# XICIE_DISPLAY_revA.net
KiCad netlist of a schematic drawn in EAGLE
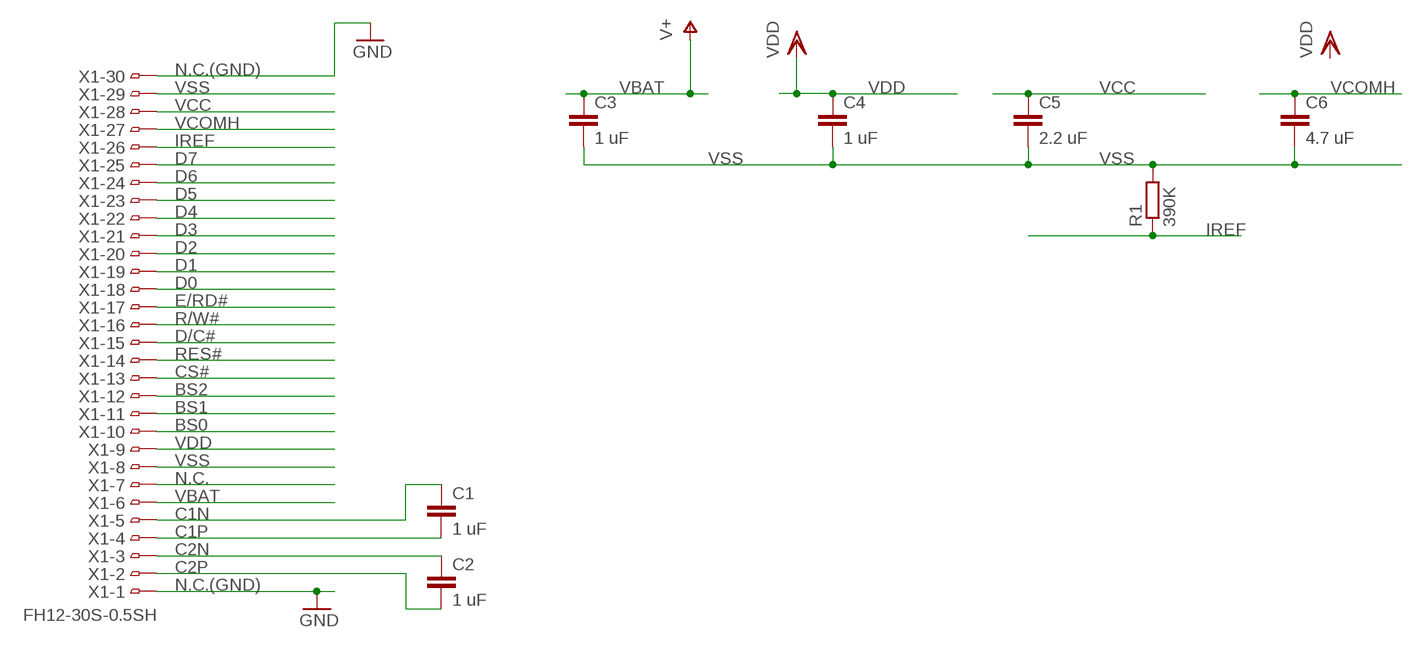
[diagram p0: schematic, sheet 1]

(export (version "E")
  (design (tool "Eeschema 10.0.6"))
  (components
    (comp (ref "C1")
      (value "1 uF")
      (footprint "eagle-import:C0402")
      (libsource (lib "eagle-import") (part "C-EUC0402"))
    )
    (comp (ref "C2")
      (value "1 uF")
      (footprint "eagle-import:C0402")
      (libsource (lib "eagle-import") (part "C-EUC0402"))
    )
    (comp (ref "C3")
      (value "1 uF")
      (footprint "eagle-import:C0402")
      (libsource (lib "eagle-import") (part "C-EUC0402"))
    )
    (comp (ref "C4")
      (value "1 uF")
      (footprint "eagle-import:C0402")
      (libsource (lib "eagle-import") (part "C-EUC0402"))
    )
    (comp (ref "C5")
      (value "2.2 uF")
      (footprint "eagle-import:C0603")
      (libsource (lib "eagle-import") (part "C-EUC0603"))
    )
    (comp (ref "C6")
      (value "4.7 uF")
      (footprint "eagle-import:C0603")
      (libsource (lib "eagle-import") (part "C-EUC0603"))
    )
    (comp (ref "R1")
      (value "390K")
      (footprint "eagle-import:R0603")
      (libsource (lib "eagle-import") (part "R-EU_R0603"))
    )
    (comp (ref "X1")
      (value "FH12-30S-0.5SH")
      (footprint "eagle-import:FH12-30S-0.5SH")
      (fields (field (name "MPN") "FH12-30S-0.5SH(55)"))
      (libsource (lib "eagle-import") (part "FH12-30S-0.5SH"))
    )
  )
  (nets
    (net (code "1") (name "/BS0") (class "Default")
      (node (ref "X1") (pin "10") (pinfunction "1_10") (pintype "passive"))
    )
    (net (code "2") (name "/BS1") (class "Default")
      (node (ref "X1") (pin "11") (pinfunction "1_11") (pintype "passive"))
    )
    (net (code "3") (name "/BS2") (class "Default")
      (node (ref "X1") (pin "12") (pinfunction "1_12") (pintype "passive"))
    )
    (net (code "4") (name "/C1N") (class "Default")
      (node (ref "C1") (pin "1") (pinfunction "1_1") (pintype "passive"))
      (node (ref "X1") (pin "5") (pinfunction "1_5") (pintype "passive"))
    )
    (net (code "5") (name "/C1P") (class "Default")
      (node (ref "C1") (pin "2") (pinfunction "2_2") (pintype "passive"))
      (node (ref "X1") (pin "4") (pinfunction "1_4") (pintype "passive"))
    )
    (net (code "6") (name "/C2N") (class "Default")
      (node (ref "C2") (pin "1") (pinfunction "1_1") (pintype "passive"))
      (node (ref "X1") (pin "3") (pinfunction "1_3") (pintype "passive"))
    )
    (net (code "7") (name "/C2P") (class "Default")
      (node (ref "C2") (pin "2") (pinfunction "2_2") (pintype "passive"))
      (node (ref "X1") (pin "2") (pinfunction "1_2") (pintype "passive"))
    )
    (net (code "8") (name "/CS#") (class "Default")
      (node (ref "X1") (pin "13") (pinfunction "1_13") (pintype "passive"))
    )
    (net (code "9") (name "/D0") (class "Default")
      (node (ref "X1") (pin "18") (pinfunction "1_18") (pintype "passive"))
    )
    (net (code "10") (name "/D1") (class "Default")
      (node (ref "X1") (pin "19") (pinfunction "1_19") (pintype "passive"))
    )
    (net (code "11") (name "/D2") (class "Default")
      (node (ref "X1") (pin "20") (pinfunction "1_20") (pintype "passive"))
    )
    (net (code "12") (name "/D3") (class "Default")
      (node (ref "X1") (pin "21") (pinfunction "1_21") (pintype "passive"))
    )
    (net (code "13") (name "/D4") (class "Default")
      (node (ref "X1") (pin "22") (pinfunction "1_22") (pintype "passive"))
    )
    (net (code "14") (name "/D5") (class "Default")
      (node (ref "X1") (pin "23") (pinfunction "1_23") (pintype "passive"))
    )
    (net (code "15") (name "/D6") (class "Default")
      (node (ref "X1") (pin "24") (pinfunction "1_24") (pintype "passive"))
    )
    (net (code "16") (name "/D7") (class "Default")
      (node (ref "X1") (pin "25") (pinfunction "1_25") (pintype "passive"))
    )
    (net (code "17") (name "/D{slash}C#") (class "Default")
      (node (ref "X1") (pin "15") (pinfunction "1_15") (pintype "passive"))
    )
    (net (code "18") (name "/E{slash}RD#") (class "Default")
      (node (ref "X1") (pin "17") (pinfunction "1_17") (pintype "passive"))
    )
    (net (code "19") (name "/IREF") (class "Default")
      (node (ref "R1") (pin "1") (pinfunction "1_1") (pintype "passive"))
      (node (ref "X1") (pin "26") (pinfunction "1_26") (pintype "passive"))
    )
    (net (code "20") (name "/N.C.") (class "Default")
      (node (ref "X1") (pin "7") (pinfunction "1_7") (pintype "passive"))
    )
    (net (code "21") (name "/RES#") (class "Default")
      (node (ref "X1") (pin "14") (pinfunction "1_14") (pintype "passive"))
    )
    (net (code "22") (name "/R{slash}W#") (class "Default")
      (node (ref "X1") (pin "16") (pinfunction "1_16") (pintype "passive"))
    )
    (net (code "23") (name "/VCC") (class "Default")
      (node (ref "C5") (pin "1") (pinfunction "1_1") (pintype "passive"))
      (node (ref "X1") (pin "28") (pinfunction "1_28") (pintype "passive"))
    )
    (net (code "24") (name "/VCOMH") (class "Default")
      (node (ref "C6") (pin "1") (pinfunction "1_1") (pintype "passive"))
      (node (ref "X1") (pin "27") (pinfunction "1_27") (pintype "passive"))
    )
    (net (code "25") (name "/VSS") (class "Default")
      (node (ref "C3") (pin "2") (pinfunction "2_2") (pintype "passive"))
      (node (ref "C4") (pin "2") (pinfunction "2_2") (pintype "passive"))
      (node (ref "C5") (pin "2") (pinfunction "2_2") (pintype "passive"))
      (node (ref "C6") (pin "2") (pinfunction "2_2") (pintype "passive"))
      (node (ref "R1") (pin "2") (pinfunction "2_2") (pintype "passive"))
      (node (ref "X1") (pin "29") (pinfunction "1_29") (pintype "passive"))
      (node (ref "X1") (pin "8") (pinfunction "1_8") (pintype "passive"))
    )
    (net (code "26") (name "GND") (class "Default")
      (node (ref "X1") (pin "1") (pinfunction "1_1") (pintype "passive"))
      (node (ref "X1") (pin "30") (pinfunction "1_30") (pintype "passive"))
    )
    (net (code "27") (name "V+") (class "Default")
      (node (ref "C3") (pin "1") (pinfunction "1_1") (pintype "passive"))
      (node (ref "X1") (pin "6") (pinfunction "1_6") (pintype "passive"))
    )
    (net (code "28") (name "VDD") (class "Default")
      (node (ref "C4") (pin "1") (pinfunction "1_1") (pintype "passive"))
      (node (ref "X1") (pin "9") (pinfunction "1_9") (pintype "passive"))
    )
  )
)
